# interposer-breakout.net
KiCad netlist of a schematic drawn in Altium Designer
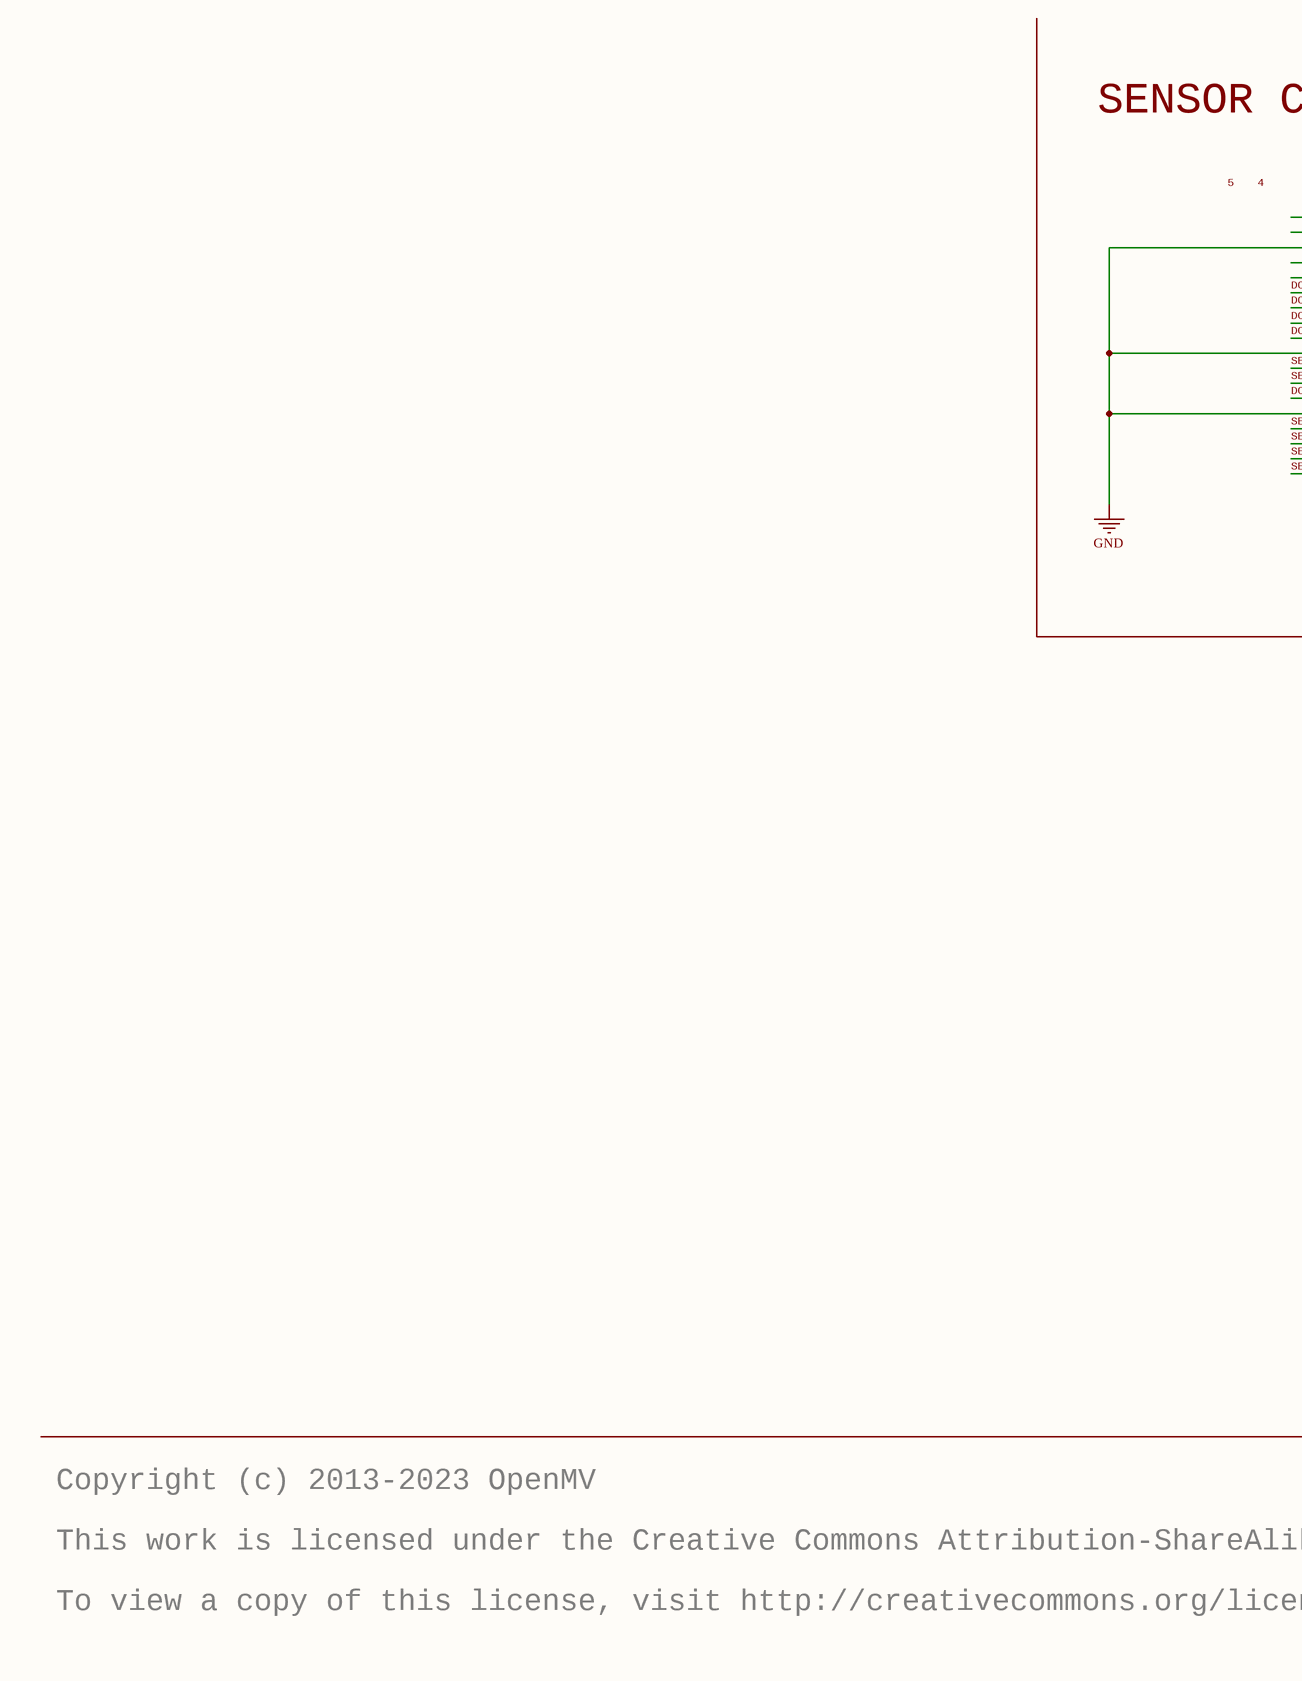
[diagram p0: interposer-breakout.SchDoc, left]
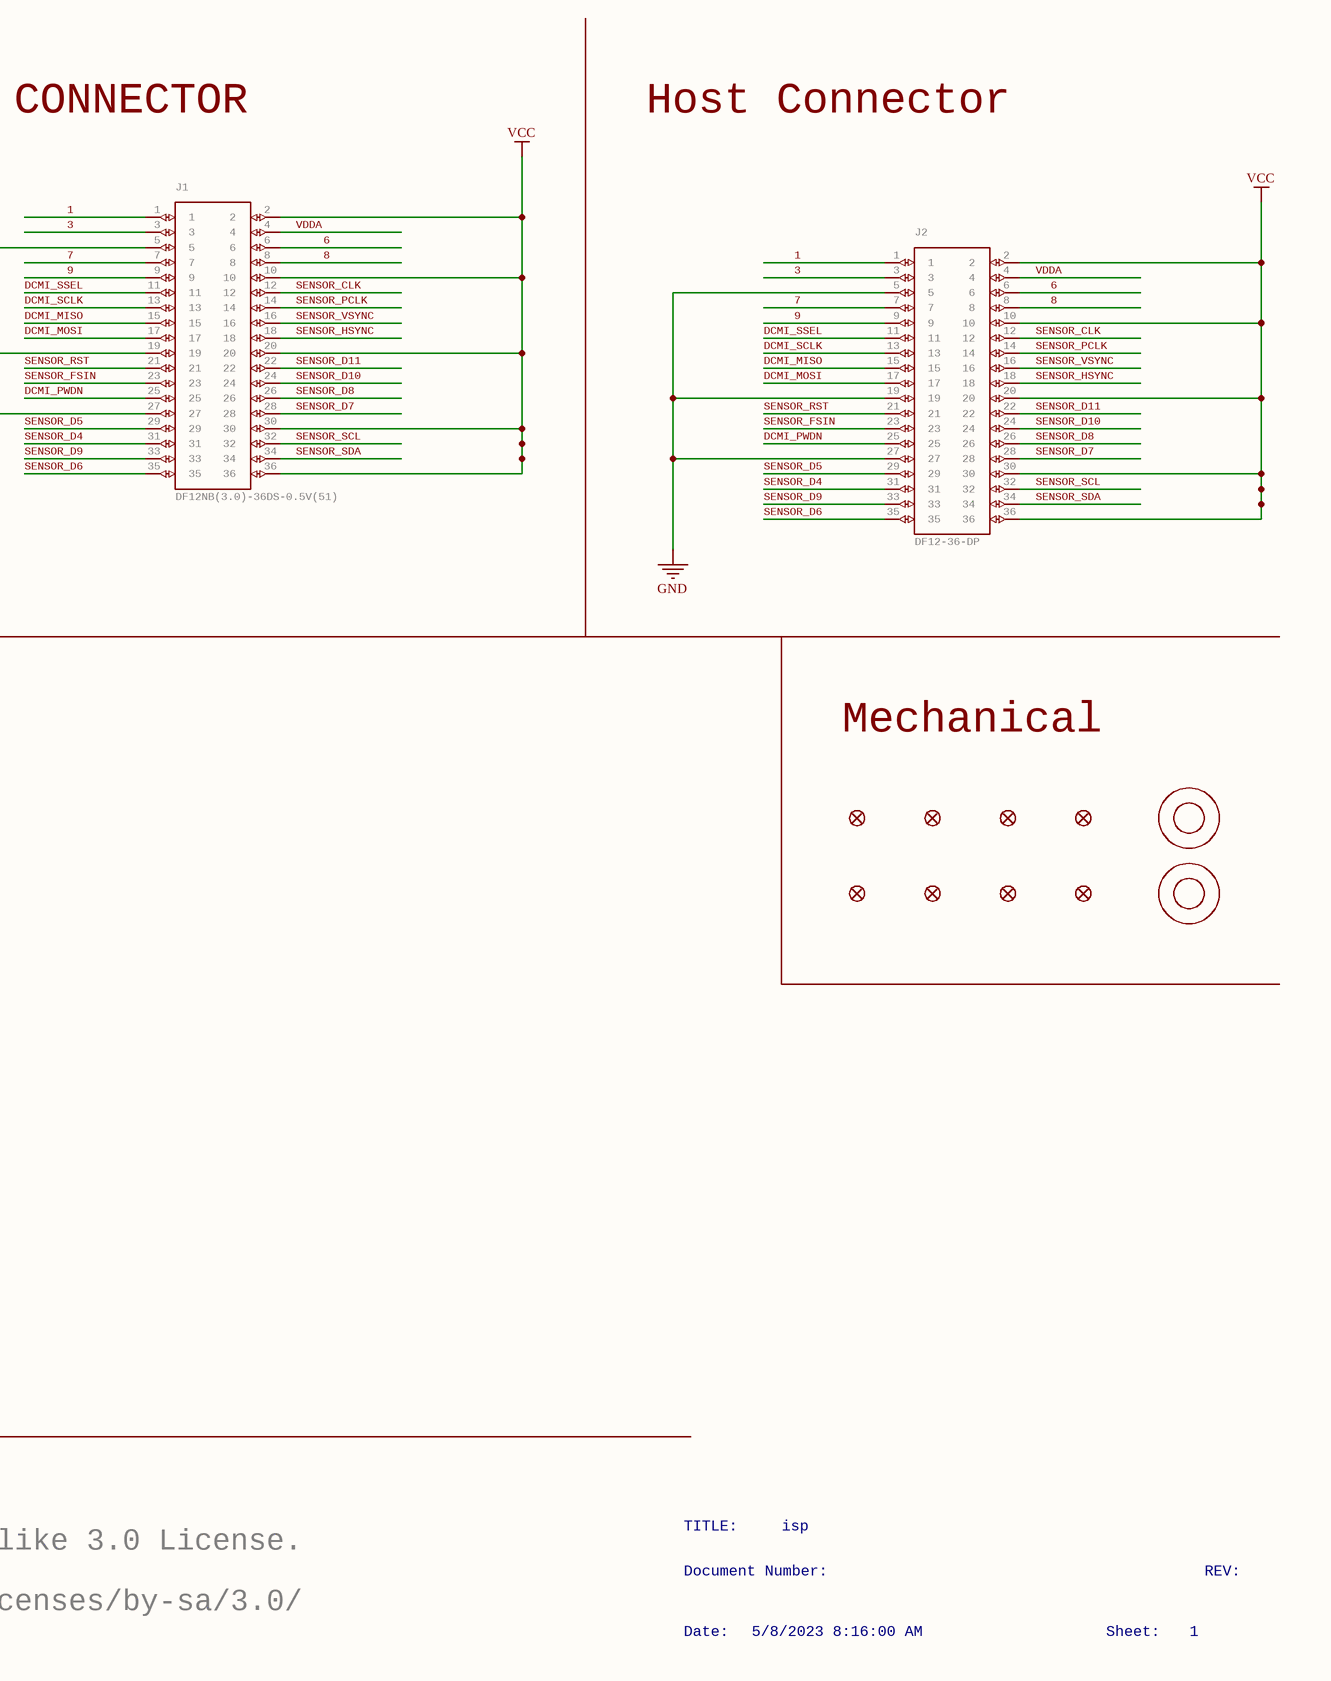
[diagram p1: interposer-breakout.SchDoc, right]

(export (version "E")
  (design (tool "Eeschema 10.0.6"))
  (components
    (comp (ref "FD1")
      (value "FIDUCIAL1X2")
      (footprint "FIDUCIAL-1X2")
      (fields (field (name "LIBRARYNAME") "SparkFun-Aesthetics"))
      (libsource (lib "camera-modules") (part "FIDUCIAL1X2"))
    )
    (comp (ref "FD2")
      (value "FIDUCIAL1X2")
      (footprint "FIDUCIAL-1X2")
      (fields (field (name "LIBRARYNAME") "SparkFun-Aesthetics"))
      (libsource (lib "camera-modules") (part "FIDUCIAL1X2"))
    )
    (comp (ref "FD3")
      (value "FIDUCIAL1X2")
      (footprint "FIDUCIAL-1X2")
      (fields (field (name "LIBRARYNAME") "SparkFun-Aesthetics"))
      (libsource (lib "camera-modules") (part "FIDUCIAL1X2"))
    )
    (comp (ref "FD4")
      (value "FIDUCIAL1X2")
      (footprint "FIDUCIAL-1X2")
      (fields (field (name "LIBRARYNAME") "SparkFun-Aesthetics"))
      (libsource (lib "camera-modules") (part "FIDUCIAL1X2"))
    )
    (comp (ref "FD5")
      (value "FIDUCIAL1X2")
      (footprint "FIDUCIAL-1X2")
      (fields (field (name "LIBRARYNAME") "SparkFun-Aesthetics"))
      (libsource (lib "camera-modules") (part "FIDUCIAL1X2"))
    )
    (comp (ref "FD6")
      (value "FIDUCIAL1X2")
      (footprint "FIDUCIAL-1X2")
      (fields (field (name "LIBRARYNAME") "SparkFun-Aesthetics"))
      (libsource (lib "camera-modules") (part "FIDUCIAL1X2"))
    )
    (comp (ref "FD7")
      (value "FIDUCIAL1X2")
      (footprint "FIDUCIAL-1X2")
      (fields (field (name "LIBRARYNAME") "SparkFun-Aesthetics"))
      (libsource (lib "camera-modules") (part "FIDUCIAL1X2"))
    )
    (comp (ref "FD8")
      (value "FIDUCIAL1X2")
      (footprint "FIDUCIAL-1X2")
      (fields (field (name "LIBRARYNAME") "SparkFun-Aesthetics"))
      (libsource (lib "camera-modules") (part "FIDUCIAL1X2"))
    )
    (comp (ref "J1")
      (value "DF12NB(3.0)-36DS-0.5V(51)")
      (footprint "DF12-36-DS")
      (libsource (lib "camera-modules") (part "DF12-36-DS"))
    )
    (comp (ref "J2")
      (value "DF12-36-DP")
      (footprint "DF12-36-DP")
      (fields (field (name "MPN") "DF12NB(3.0)-36DP-0.5V(51)"))
      (libsource (lib "camera-modules") (part "DF12-36-DP"))
    )
    (comp (ref "M1")
      (value "9774030151R")
      (footprint "9774030243R")
      (libsource (lib "camera-modules") (part "9774030151R"))
    )
    (comp (ref "M2")
      (value "9774030151R")
      (footprint "9774030243R")
      (libsource (lib "camera-modules") (part "9774030151R"))
    )
  )
  (nets
    (net (code "1") (name "/1") (class "Default")
      (node (ref "J1") (pin "1") (pinfunction "1_1") (pintype "bidirectional"))
      (node (ref "J2") (pin "1") (pinfunction "1_1") (pintype "bidirectional"))
    )
    (net (code "2") (name "/3") (class "Default")
      (node (ref "J1") (pin "3") (pinfunction "3_3") (pintype "bidirectional"))
      (node (ref "J2") (pin "3") (pinfunction "3_3") (pintype "bidirectional"))
    )
    (net (code "5") (name "/6") (class "Default")
      (node (ref "J1") (pin "6") (pinfunction "6_6") (pintype "bidirectional"))
      (node (ref "J2") (pin "6") (pinfunction "6_6") (pintype "bidirectional"))
    )
    (net (code "6") (name "/7") (class "Default")
      (node (ref "J1") (pin "7") (pinfunction "7_7") (pintype "bidirectional"))
      (node (ref "J2") (pin "7") (pinfunction "7_7") (pintype "bidirectional"))
    )
    (net (code "7") (name "/8") (class "Default")
      (node (ref "J1") (pin "8") (pinfunction "8_8") (pintype "bidirectional"))
      (node (ref "J2") (pin "8") (pinfunction "8_8") (pintype "bidirectional"))
    )
    (net (code "8") (name "/9") (class "Default")
      (node (ref "J1") (pin "9") (pinfunction "9_9") (pintype "bidirectional"))
      (node (ref "J2") (pin "9") (pinfunction "9_9") (pintype "bidirectional"))
    )
    (net (code "9") (name "/DCMI_MISO") (class "Default")
      (node (ref "J1") (pin "15") (pinfunction "15_15") (pintype "bidirectional"))
      (node (ref "J2") (pin "15") (pinfunction "15_15") (pintype "bidirectional"))
    )
    (net (code "10") (name "/DCMI_MOSI") (class "Default")
      (node (ref "J1") (pin "17") (pinfunction "17_17") (pintype "bidirectional"))
      (node (ref "J2") (pin "17") (pinfunction "17_17") (pintype "bidirectional"))
    )
    (net (code "11") (name "/DCMI_PWDN") (class "Default")
      (node (ref "J1") (pin "25") (pinfunction "25_25") (pintype "bidirectional"))
      (node (ref "J2") (pin "25") (pinfunction "25_25") (pintype "bidirectional"))
    )
    (net (code "12") (name "/DCMI_SCLK") (class "Default")
      (node (ref "J1") (pin "13") (pinfunction "13_13") (pintype "bidirectional"))
      (node (ref "J2") (pin "13") (pinfunction "13_13") (pintype "bidirectional"))
    )
    (net (code "13") (name "/DCMI_SSEL") (class "Default")
      (node (ref "J1") (pin "11") (pinfunction "11_11") (pintype "bidirectional"))
      (node (ref "J2") (pin "11") (pinfunction "11_11") (pintype "bidirectional"))
    )
    (net (code "14") (name "/SENSOR_CLK") (class "Default")
      (node (ref "J1") (pin "12") (pinfunction "12_12") (pintype "bidirectional"))
      (node (ref "J2") (pin "12") (pinfunction "12_12") (pintype "bidirectional"))
    )
    (net (code "15") (name "/SENSOR_D4") (class "Default")
      (node (ref "J1") (pin "31") (pinfunction "31_31") (pintype "bidirectional"))
      (node (ref "J2") (pin "31") (pinfunction "31_31") (pintype "bidirectional"))
    )
    (net (code "16") (name "/SENSOR_D5") (class "Default")
      (node (ref "J1") (pin "29") (pinfunction "29_29") (pintype "bidirectional"))
      (node (ref "J2") (pin "29") (pinfunction "29_29") (pintype "bidirectional"))
    )
    (net (code "17") (name "/SENSOR_D6") (class "Default")
      (node (ref "J1") (pin "35") (pinfunction "35_35") (pintype "bidirectional"))
      (node (ref "J2") (pin "35") (pinfunction "35_35") (pintype "bidirectional"))
    )
    (net (code "18") (name "/SENSOR_D7") (class "Default")
      (node (ref "J1") (pin "28") (pinfunction "28_28") (pintype "bidirectional"))
      (node (ref "J2") (pin "28") (pinfunction "28_28") (pintype "bidirectional"))
    )
    (net (code "19") (name "/SENSOR_D8") (class "Default")
      (node (ref "J1") (pin "26") (pinfunction "26_26") (pintype "bidirectional"))
      (node (ref "J2") (pin "26") (pinfunction "26_26") (pintype "bidirectional"))
    )
    (net (code "20") (name "/SENSOR_D9") (class "Default")
      (node (ref "J1") (pin "33") (pinfunction "33_33") (pintype "bidirectional"))
      (node (ref "J2") (pin "33") (pinfunction "33_33") (pintype "bidirectional"))
    )
    (net (code "21") (name "/SENSOR_D10") (class "Default")
      (node (ref "J1") (pin "24") (pinfunction "24_24") (pintype "bidirectional"))
      (node (ref "J2") (pin "24") (pinfunction "24_24") (pintype "bidirectional"))
    )
    (net (code "22") (name "/SENSOR_D11") (class "Default")
      (node (ref "J1") (pin "22") (pinfunction "22_22") (pintype "bidirectional"))
      (node (ref "J2") (pin "22") (pinfunction "22_22") (pintype "bidirectional"))
    )
    (net (code "23") (name "/SENSOR_FSIN") (class "Default")
      (node (ref "J1") (pin "23") (pinfunction "23_23") (pintype "bidirectional"))
      (node (ref "J2") (pin "23") (pinfunction "23_23") (pintype "bidirectional"))
    )
    (net (code "24") (name "/SENSOR_HSYNC") (class "Default")
      (node (ref "J1") (pin "18") (pinfunction "18_18") (pintype "bidirectional"))
      (node (ref "J2") (pin "18") (pinfunction "18_18") (pintype "bidirectional"))
    )
    (net (code "25") (name "/SENSOR_PCLK") (class "Default")
      (node (ref "J1") (pin "14") (pinfunction "14_14") (pintype "bidirectional"))
      (node (ref "J2") (pin "14") (pinfunction "14_14") (pintype "bidirectional"))
    )
    (net (code "26") (name "/SENSOR_RST") (class "Default")
      (node (ref "J1") (pin "21") (pinfunction "21_21") (pintype "bidirectional"))
      (node (ref "J2") (pin "21") (pinfunction "21_21") (pintype "bidirectional"))
    )
    (net (code "27") (name "/SENSOR_SCL") (class "Default")
      (node (ref "J1") (pin "32") (pinfunction "32_32") (pintype "bidirectional"))
      (node (ref "J2") (pin "32") (pinfunction "32_32") (pintype "bidirectional"))
    )
    (net (code "28") (name "/SENSOR_SDA") (class "Default")
      (node (ref "J1") (pin "34") (pinfunction "34_34") (pintype "bidirectional"))
      (node (ref "J2") (pin "34") (pinfunction "34_34") (pintype "bidirectional"))
    )
    (net (code "29") (name "/SENSOR_VSYNC") (class "Default")
      (node (ref "J1") (pin "16") (pinfunction "16_16") (pintype "bidirectional"))
      (node (ref "J2") (pin "16") (pinfunction "16_16") (pintype "bidirectional"))
    )
    (net (code "30") (name "/VDDA") (class "Default")
      (node (ref "J1") (pin "4") (pinfunction "4_4") (pintype "bidirectional"))
      (node (ref "J2") (pin "4") (pinfunction "4_4") (pintype "bidirectional"))
    )
    (net (code "31") (name "GND") (class "Default")
      (node (ref "J1") (pin "19") (pinfunction "19_19") (pintype "bidirectional"))
      (node (ref "J1") (pin "27") (pinfunction "27_27") (pintype "bidirectional"))
      (node (ref "J1") (pin "5") (pinfunction "5_5") (pintype "bidirectional"))
      (node (ref "J2") (pin "19") (pinfunction "19_19") (pintype "bidirectional"))
      (node (ref "J2") (pin "27") (pinfunction "27_27") (pintype "bidirectional"))
      (node (ref "J2") (pin "5") (pinfunction "5_5") (pintype "bidirectional"))
    )
    (net (code "32") (name "VCC") (class "Default")
      (node (ref "J1") (pin "10") (pinfunction "10_10") (pintype "bidirectional"))
      (node (ref "J1") (pin "2") (pinfunction "2_2") (pintype "bidirectional"))
      (node (ref "J1") (pin "20") (pinfunction "20_20") (pintype "bidirectional"))
      (node (ref "J1") (pin "30") (pinfunction "30_30") (pintype "bidirectional"))
      (node (ref "J1") (pin "36") (pinfunction "36_36") (pintype "bidirectional"))
      (node (ref "J2") (pin "10") (pinfunction "10_10") (pintype "bidirectional"))
      (node (ref "J2") (pin "2") (pinfunction "2_2") (pintype "bidirectional"))
      (node (ref "J2") (pin "20") (pinfunction "20_20") (pintype "bidirectional"))
      (node (ref "J2") (pin "30") (pinfunction "30_30") (pintype "bidirectional"))
      (node (ref "J2") (pin "36") (pinfunction "36_36") (pintype "bidirectional"))
    )
  )
)
